# PCB_main.net
KiCad netlist of a schematic drawn in Altium Designer
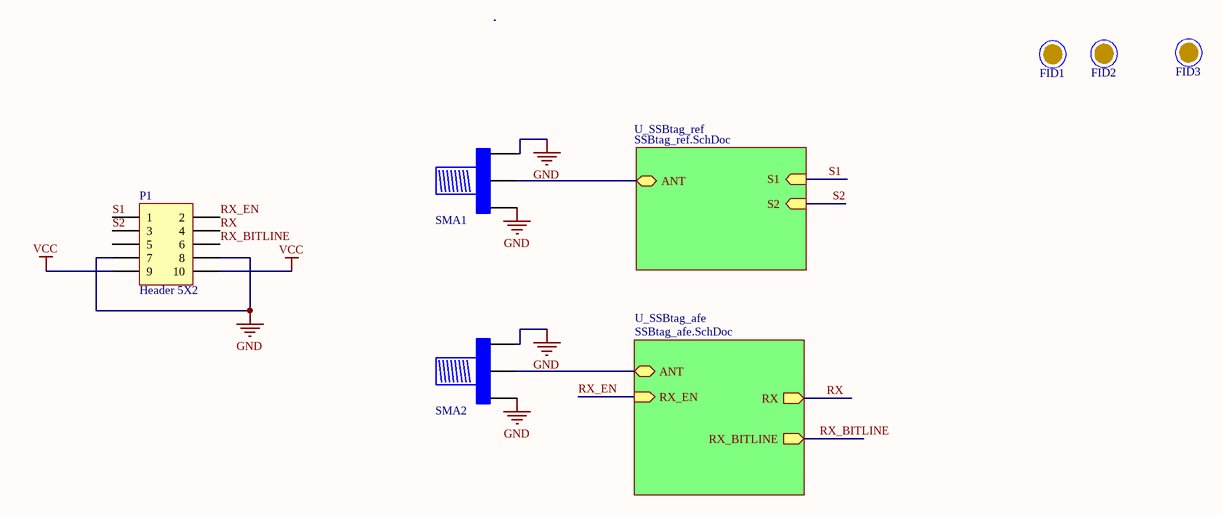
[diagram p0: PCB_main.SchDoc]

(export (version "E")
  (design (tool "Eeschema 10.0.6"))
  (components
    (comp (ref "FID1") (value "Fiducial") (footprint "Fiducial10-20") (libsource (lib "bfp") (part "FID")))
    (comp (ref "FID2") (value "Fiducial") (footprint "Fiducial10-20") (libsource (lib "bfp") (part "FID")))
    (comp (ref "FID3") (value "Fiducial") (footprint "Fiducial10-20") (libsource (lib "bfp") (part "FID")))
    (comp (ref "P1")
      (value "Header 5X2")
      (footprint "HDR2X5")
      (description "Header, 5-Pin, Dual row")
      (fields (field (name "PUBLISHER") "Altium Limited"))
      (libsource (lib "Miscellaneous Connectors") (part "Header 5X2"))
    )
    (comp (ref "SMA1")
      (value "SMA - Edge")
      (footprint "SMA - Edge - Wide")
      (description "SMA - Board Edge Connector")
      (libsource (lib "bfp") (part "SMA - Edge"))
    )
    (comp (ref "SMA2")
      (value "SMA - Edge")
      (footprint "SMA - Edge - Wide")
      (description "SMA - Board Edge Connector")
      (libsource (lib "bfp") (part "SMA - Edge"))
    )
  )
  (nets
    (net (code "1") (name "/ANT") (class "Default")
      (node (ref "SMA2") (pin "2") (pinfunction "2_2") (pintype "passive"))
    )
    (net (code "2") (name "/ANT_1") (class "Default")
      (node (ref "SMA1") (pin "2") (pinfunction "2_2") (pintype "passive"))
    )
    (net (code "3") (name "/RX") (class "Default")
      (node (ref "P1") (pin "4") (pinfunction "4_4") (pintype "passive"))
    )
    (net (code "4") (name "/RX_BITLINE") (class "Default")
      (node (ref "P1") (pin "6") (pinfunction "6_6") (pintype "passive"))
    )
    (net (code "5") (name "/RX_EN") (class "Default")
      (node (ref "P1") (pin "2") (pinfunction "2_2") (pintype "passive"))
    )
    (net (code "6") (name "/S1") (class "Default")
      (node (ref "P1") (pin "1") (pinfunction "1_1") (pintype "passive"))
    )
    (net (code "7") (name "/S2") (class "Default")
      (node (ref "P1") (pin "3") (pinfunction "3_3") (pintype "passive"))
    )
    (net (code "8") (name "GND") (class "Default")
      (node (ref "P1") (pin "7") (pinfunction "7_7") (pintype "passive"))
      (node (ref "P1") (pin "8") (pinfunction "8_8") (pintype "passive"))
      (node (ref "SMA1") (pin "1") (pinfunction "1_1") (pintype "passive"))
      (node (ref "SMA2") (pin "1") (pinfunction "1_1") (pintype "passive"))
    )
    (net (code "9") (name "VCC") (class "Default")
      (node (ref "P1") (pin "10") (pinfunction "10_10") (pintype "passive"))
      (node (ref "P1") (pin "9") (pinfunction "9_9") (pintype "passive"))
    )
    (net (code "10") (name "unconnected-(P1-Pad5)") (class "Default")
      (node (ref "P1") (pin "5") (pinfunction "5_5") (pintype "passive"))
    )
  )
)
